# Toggle.net
KiCad netlist of a schematic drawn in EAGLE
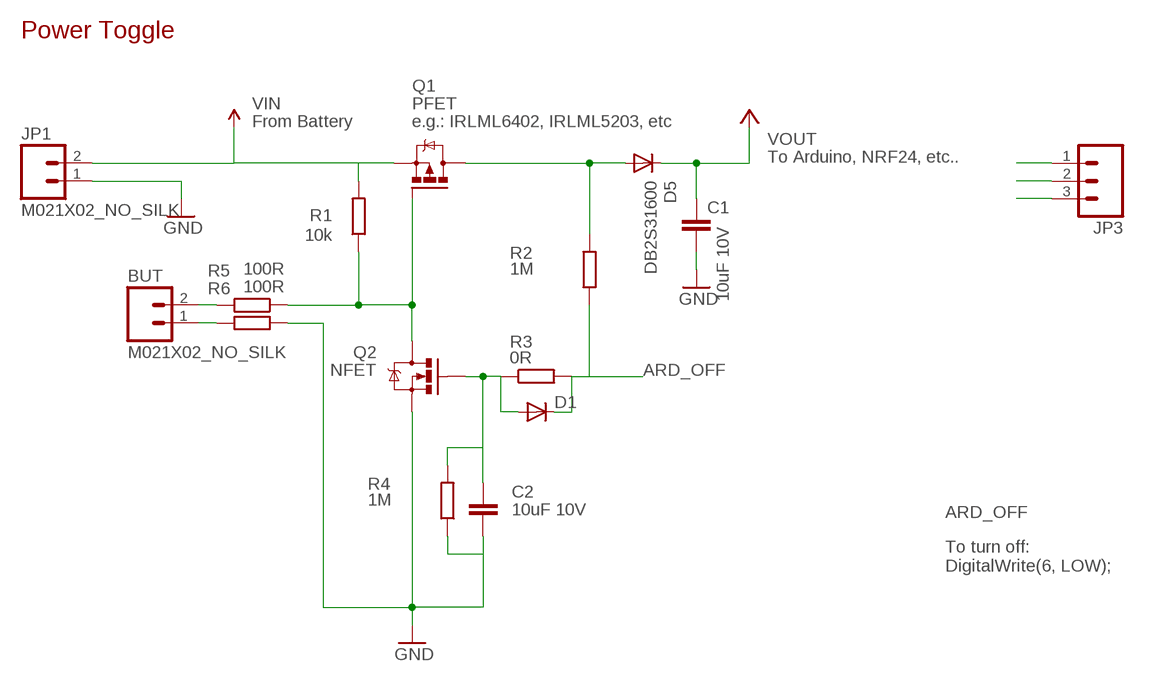
[diagram p0: schematic, sheet 1]

(export (version "E")
  (design (tool "Eeschema 10.0.6"))
  (components
    (comp (ref "BUT")
      (value "M021X02_NO_SILK")
      (footprint "eagle-import:1X02_NO_SILK")
      (libsource (lib "eagle-import") (part "M021X02_NO_SILK"))
    )
    (comp (ref "C1")
      (value "10uF 10V")
      (footprint "eagle-import:C0805")
      (libsource (lib "eagle-import") (part "C-EUC0805"))
    )
    (comp (ref "C2")
      (value "10uF 10V")
      (footprint "eagle-import:C0805")
      (libsource (lib "eagle-import") (part "C-EUC0805"))
    )
    (comp (ref "D1")
      (value "DIODESOD523")
      (footprint "eagle-import:SOD523")
      (libsource (lib "eagle-import") (part "DIODESOD523"))
    )
    (comp (ref "D5")
      (value "DB2S31600")
      (footprint "eagle-import:SMA-DIODE")
      (libsource (lib "eagle-import") (part "DIODESMA"))
    )
    (comp (ref "JP1")
      (value "M021X02_NO_SILK")
      (footprint "eagle-import:1X02_NO_SILK")
      (libsource (lib "eagle-import") (part "M021X02_NO_SILK"))
    )
    (comp (ref "JP3")
      (value "M031X03_NO_SILK")
      (footprint "eagle-import:1X03_NO_SILK")
      (libsource (lib "eagle-import") (part "M031X03_NO_SILK"))
    )
    (comp (ref "Q1")
      (value "PFET")
      (footprint "eagle-import:MICRO3")
      (libsource (lib "eagle-import") (part "IRLML5203"))
    )
    (comp (ref "Q2")
      (value "NFET")
      (footprint "eagle-import:SOT23")
      (libsource (lib "eagle-import") (part "MOSFET-NCHANNELBSS123LT1G"))
    )
    (comp (ref "R1")
      (value "10k")
      (footprint "eagle-import:R0603")
      (libsource (lib "eagle-import") (part "R-EU_R0603"))
    )
    (comp (ref "R2")
      (value "1M")
      (footprint "eagle-import:R0603")
      (libsource (lib "eagle-import") (part "R-EU_R0603"))
    )
    (comp (ref "R3")
      (value "0R")
      (footprint "eagle-import:R0603")
      (libsource (lib "eagle-import") (part "R-EU_R0603"))
    )
    (comp (ref "R4")
      (value "1M")
      (footprint "eagle-import:R0603")
      (libsource (lib "eagle-import") (part "R-EU_R0603"))
    )
    (comp (ref "R5")
      (value "100R")
      (footprint "eagle-import:R0603")
      (libsource (lib "eagle-import") (part "R-EU_R0603"))
    )
    (comp (ref "R6")
      (value "100R")
      (footprint "eagle-import:R0603")
      (libsource (lib "eagle-import") (part "R-EU_R0603"))
    )
  )
  (nets
    (net (code "1") (name "/ARD_OFF") (class "Default")
      (node (ref "D1") (pin "C") (pinfunction "C_C") (pintype "passive"))
      (node (ref "JP3") (pin "3") (pinfunction "3_3") (pintype "passive"))
      (node (ref "R2") (pin "1") (pinfunction "1_1") (pintype "passive"))
      (node (ref "R3") (pin "2") (pinfunction "2_2") (pintype "passive"))
    )
    (net (code "2") (name "GND") (class "Default")
      (node (ref "C1") (pin "2") (pinfunction "2_2") (pintype "passive"))
      (node (ref "C2") (pin "2") (pinfunction "2_2") (pintype "passive"))
      (node (ref "JP1") (pin "1") (pinfunction "1_1") (pintype "passive"))
      (node (ref "JP3") (pin "1") (pinfunction "1_1") (pintype "passive"))
      (node (ref "Q2") (pin "2") (pinfunction "S_2") (pintype "passive"))
      (node (ref "R4") (pin "1") (pinfunction "1_1") (pintype "passive"))
      (node (ref "R6") (pin "1") (pinfunction "1_1") (pintype "passive"))
    )
    (net (code "3") (name "Net-(BUT-Pad1)") (class "Default")
      (node (ref "BUT") (pin "1") (pinfunction "1_1") (pintype "passive"))
      (node (ref "R6") (pin "2") (pinfunction "2_2") (pintype "passive"))
    )
    (net (code "4") (name "Net-(BUT-Pad2)") (class "Default")
      (node (ref "BUT") (pin "2") (pinfunction "2_2") (pintype "passive"))
      (node (ref "R5") (pin "2") (pinfunction "2_2") (pintype "passive"))
    )
    (net (code "5") (name "Net-(Q1-D)") (class "Default")
      (node (ref "D5") (pin "A") (pinfunction "A_A") (pintype "passive"))
      (node (ref "Q1") (pin "3") (pinfunction "D_3") (pintype "passive"))
      (node (ref "R2") (pin "2") (pinfunction "2_2") (pintype "passive"))
    )
    (net (code "6") (name "Net-(Q1-G)") (class "Default")
      (node (ref "Q1") (pin "1") (pinfunction "G_1") (pintype "passive"))
      (node (ref "Q2") (pin "3") (pinfunction "D_3") (pintype "passive"))
      (node (ref "R1") (pin "1") (pinfunction "1_1") (pintype "passive"))
      (node (ref "R5") (pin "1") (pinfunction "1_1") (pintype "passive"))
    )
    (net (code "7") (name "Net-(Q2-G)") (class "Default")
      (node (ref "C2") (pin "1") (pinfunction "1_1") (pintype "passive"))
      (node (ref "D1") (pin "A") (pinfunction "A_A") (pintype "passive"))
      (node (ref "Q2") (pin "1") (pinfunction "G_1") (pintype "passive"))
      (node (ref "R3") (pin "1") (pinfunction "1_1") (pintype "passive"))
      (node (ref "R4") (pin "2") (pinfunction "2_2") (pintype "passive"))
    )
    (net (code "8") (name "VCC") (class "Default")
      (node (ref "C1") (pin "1") (pinfunction "1_1") (pintype "passive"))
      (node (ref "D5") (pin "C") (pinfunction "C_C") (pintype "passive"))
      (node (ref "JP3") (pin "2") (pinfunction "2_2") (pintype "passive"))
    )
    (net (code "9") (name "VIN") (class "Default")
      (node (ref "JP1") (pin "2") (pinfunction "2_2") (pintype "passive"))
      (node (ref "Q1") (pin "2") (pinfunction "S_2") (pintype "passive"))
      (node (ref "R1") (pin "2") (pinfunction "2_2") (pintype "passive"))
    )
  )
)
